# nekojara_board.net
KiCad netlist of a schematic drawn in EAGLE
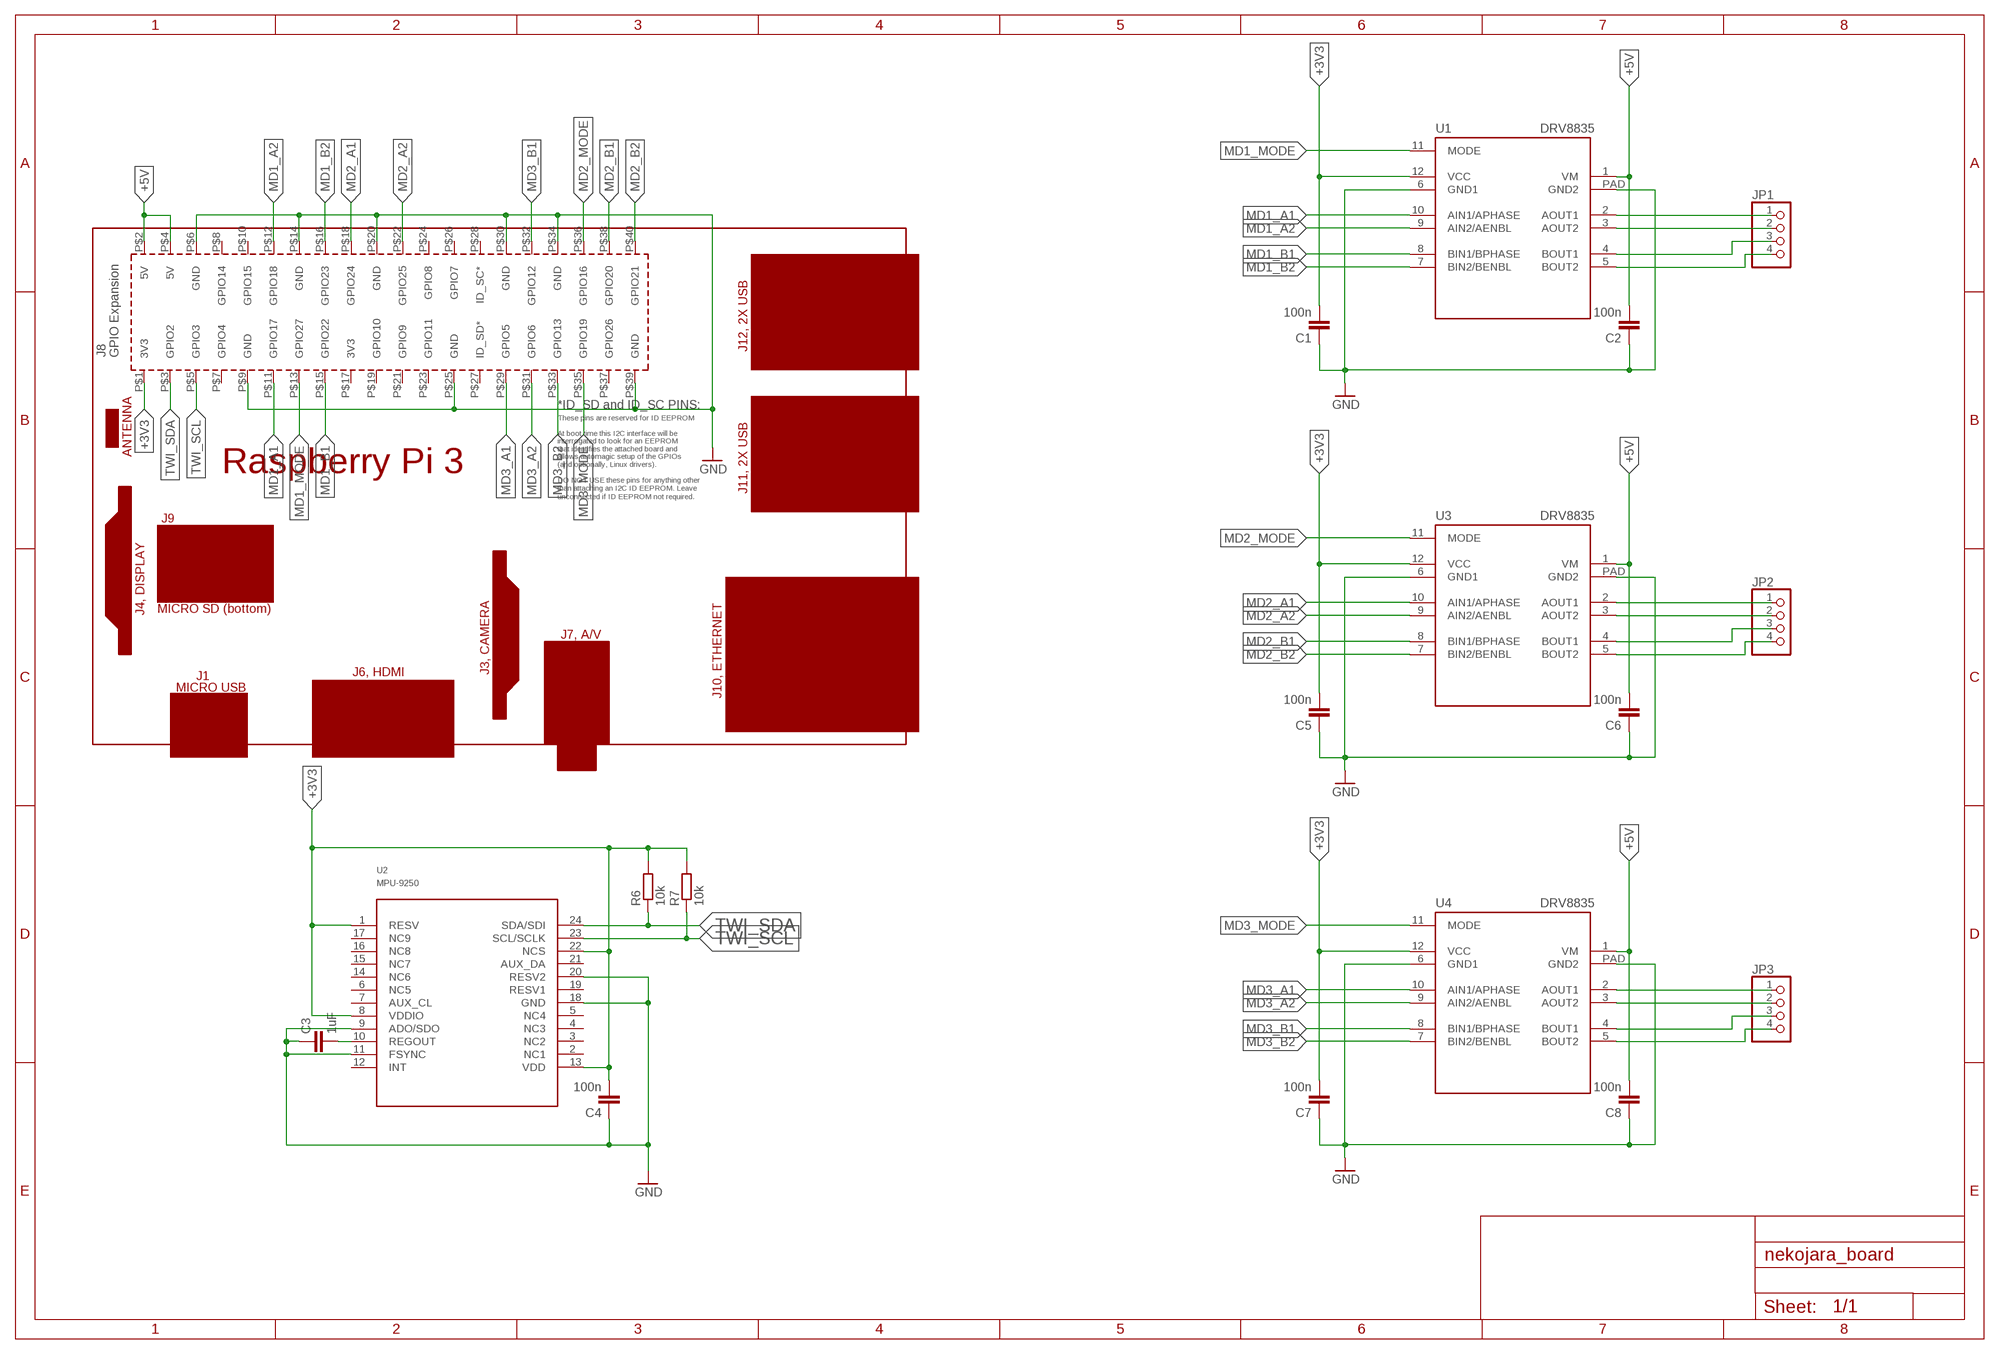
[diagram p0: schematic, sheet 1]

(export (version "E")
  (design (tool "Eeschema 10.0.6"))
  (components
    (comp (ref "C1")
      (value "100n")
      (footprint "eagle-import:C0402")
      (libsource (lib "eagle-import") (part "C-EUC0402"))
    )
    (comp (ref "C2")
      (value "100n")
      (footprint "eagle-import:C0402")
      (libsource (lib "eagle-import") (part "C-EUC0402"))
    )
    (comp (ref "C3")
      (value "1uF")
      (footprint "eagle-import:C0402")
      (libsource (lib "eagle-import") (part "C-EUC0402"))
    )
    (comp (ref "C4")
      (value "100n")
      (footprint "eagle-import:C0402")
      (libsource (lib "eagle-import") (part "C-EUC0402"))
    )
    (comp (ref "C5")
      (value "100n")
      (footprint "eagle-import:C0402")
      (libsource (lib "eagle-import") (part "C-EUC0402"))
    )
    (comp (ref "C6")
      (value "100n")
      (footprint "eagle-import:C0402")
      (libsource (lib "eagle-import") (part "C-EUC0402"))
    )
    (comp (ref "C7")
      (value "100n")
      (footprint "eagle-import:C0402")
      (libsource (lib "eagle-import") (part "C-EUC0402"))
    )
    (comp (ref "C8")
      (value "100n")
      (footprint "eagle-import:C0402")
      (libsource (lib "eagle-import") (part "C-EUC0402"))
    )
    (comp (ref "JP1")
      (value "PINHD-1X4")
      (footprint "eagle-import:1X04")
      (libsource (lib "eagle-import") (part "PINHD-1X4"))
    )
    (comp (ref "JP2")
      (value "PINHD-1X4")
      (footprint "eagle-import:1X04")
      (libsource (lib "eagle-import") (part "PINHD-1X4"))
    )
    (comp (ref "JP3")
      (value "PINHD-1X4")
      (footprint "eagle-import:1X04")
      (libsource (lib "eagle-import") (part "PINHD-1X4"))
    )
    (comp (ref "PCB1")
      (value "RPI3")
      (footprint "eagle-import:RPI3")
      (libsource (lib "eagle-import") (part "RPI3"))
    )
    (comp (ref "R6")
      (value "10k")
      (footprint "eagle-import:R0402")
      (libsource (lib "eagle-import") (part "R-EU_R0402"))
    )
    (comp (ref "R7")
      (value "10k")
      (footprint "eagle-import:R0402")
      (libsource (lib "eagle-import") (part "R-EU_R0402"))
    )
    (comp (ref "U1")
      (value "DRV8835")
      (footprint "eagle-import:WSON_2X3")
      (libsource (lib "eagle-import") (part "DRV8835"))
    )
    (comp (ref "U2")
      (value "MPU-9250")
      (footprint "eagle-import:LEAD-QFN24")
      (libsource (lib "eagle-import") (part "MPU-9250"))
    )
    (comp (ref "U3")
      (value "DRV8835")
      (footprint "eagle-import:WSON_2X3")
      (libsource (lib "eagle-import") (part "DRV8835"))
    )
    (comp (ref "U4")
      (value "DRV8835")
      (footprint "eagle-import:WSON_2X3")
      (libsource (lib "eagle-import") (part "DRV8835"))
    )
  )
  (nets
    (net (code "1") (name "+3V3") (class "Default")
      (node (ref "C1") (pin "2") (pinfunction "2_2") (pintype "passive"))
      (node (ref "C4") (pin "2") (pinfunction "2_2") (pintype "passive"))
      (node (ref "C5") (pin "2") (pinfunction "2_2") (pintype "passive"))
      (node (ref "C7") (pin "2") (pinfunction "2_2") (pintype "passive"))
      (node (ref "PCB1") (pin "P$1") (pinfunction "3V3_P$1") (pintype "bidirectional"))
      (node (ref "R6") (pin "2") (pinfunction "2_2") (pintype "passive"))
      (node (ref "R7") (pin "2") (pinfunction "2_2") (pintype "passive"))
      (node (ref "U1") (pin "12") (pinfunction "VCC_12") (pintype "bidirectional"))
      (node (ref "U2") (pin "1") (pinfunction "RESV_1") (pintype "bidirectional"))
      (node (ref "U2") (pin "13") (pinfunction "VDD_13") (pintype "bidirectional"))
      (node (ref "U2") (pin "22") (pinfunction "NCS_22") (pintype "bidirectional"))
      (node (ref "U2") (pin "8") (pinfunction "VDDIO_8") (pintype "bidirectional"))
      (node (ref "U3") (pin "12") (pinfunction "VCC_12") (pintype "bidirectional"))
      (node (ref "U4") (pin "12") (pinfunction "VCC_12") (pintype "bidirectional"))
    )
    (net (code "2") (name "+5V") (class "Default")
      (node (ref "C2") (pin "2") (pinfunction "2_2") (pintype "passive"))
      (node (ref "C6") (pin "2") (pinfunction "2_2") (pintype "passive"))
      (node (ref "C8") (pin "2") (pinfunction "2_2") (pintype "passive"))
      (node (ref "PCB1") (pin "P$2") (pinfunction "5V_P$2") (pintype "bidirectional"))
      (node (ref "PCB1") (pin "P$4") (pinfunction "5V_P$4") (pintype "bidirectional"))
      (node (ref "U1") (pin "1") (pinfunction "VM_1") (pintype "bidirectional"))
      (node (ref "U3") (pin "1") (pinfunction "VM_1") (pintype "bidirectional"))
      (node (ref "U4") (pin "1") (pinfunction "VM_1") (pintype "bidirectional"))
    )
    (net (code "3") (name "GND") (class "Default")
      (node (ref "C1") (pin "1") (pinfunction "1_1") (pintype "passive"))
      (node (ref "C2") (pin "1") (pinfunction "1_1") (pintype "passive"))
      (node (ref "C3") (pin "1") (pinfunction "1_1") (pintype "passive"))
      (node (ref "C4") (pin "1") (pinfunction "1_1") (pintype "passive"))
      (node (ref "C5") (pin "1") (pinfunction "1_1") (pintype "passive"))
      (node (ref "C6") (pin "1") (pinfunction "1_1") (pintype "passive"))
      (node (ref "C7") (pin "1") (pinfunction "1_1") (pintype "passive"))
      (node (ref "C8") (pin "1") (pinfunction "1_1") (pintype "passive"))
      (node (ref "PCB1") (pin "P$14") (pinfunction "GND_P$14") (pintype "bidirectional"))
      (node (ref "PCB1") (pin "P$20") (pinfunction "GND_P$20") (pintype "bidirectional"))
      (node (ref "PCB1") (pin "P$25") (pinfunction "GND_P$25") (pintype "bidirectional"))
      (node (ref "PCB1") (pin "P$30") (pinfunction "GND_P$30") (pintype "bidirectional"))
      (node (ref "PCB1") (pin "P$34") (pinfunction "GND_P$34") (pintype "bidirectional"))
      (node (ref "PCB1") (pin "P$39") (pinfunction "GND_P$39") (pintype "bidirectional"))
      (node (ref "PCB1") (pin "P$6") (pinfunction "GND_P$6") (pintype "bidirectional"))
      (node (ref "PCB1") (pin "P$9") (pinfunction "GND_P$9") (pintype "bidirectional"))
      (node (ref "U1") (pin "6") (pinfunction "GND1_6") (pintype "bidirectional"))
      (node (ref "U1") (pin "PAD") (pinfunction "GND2_PAD") (pintype "bidirectional"))
      (node (ref "U2") (pin "11") (pinfunction "FSYNC_11") (pintype "bidirectional"))
      (node (ref "U2") (pin "18") (pinfunction "GND_18") (pintype "bidirectional"))
      (node (ref "U2") (pin "20") (pinfunction "RESV2_20") (pintype "bidirectional"))
      (node (ref "U2") (pin "9") (pinfunction "ADO/SDO_9") (pintype "bidirectional"))
      (node (ref "U3") (pin "6") (pinfunction "GND1_6") (pintype "bidirectional"))
      (node (ref "U3") (pin "PAD") (pinfunction "GND2_PAD") (pintype "bidirectional"))
      (node (ref "U4") (pin "6") (pinfunction "GND1_6") (pintype "bidirectional"))
      (node (ref "U4") (pin "PAD") (pinfunction "GND2_PAD") (pintype "bidirectional"))
    )
    (net (code "4") (name "MD1_A1") (class "Default")
      (node (ref "PCB1") (pin "P$11") (pinfunction "GPIO17_P$11") (pintype "bidirectional"))
      (node (ref "U1") (pin "10") (pinfunction "AIN1/APHASE_10") (pintype "bidirectional"))
    )
    (net (code "5") (name "MD1_A2") (class "Default")
      (node (ref "PCB1") (pin "P$12") (pinfunction "GPIO18_P$12") (pintype "bidirectional"))
      (node (ref "U1") (pin "9") (pinfunction "AIN2/AENBL_9") (pintype "bidirectional"))
    )
    (net (code "6") (name "MD1_B1") (class "Default")
      (node (ref "PCB1") (pin "P$15") (pinfunction "GPIO22_P$15") (pintype "bidirectional"))
      (node (ref "U1") (pin "8") (pinfunction "BIN1/BPHASE_8") (pintype "bidirectional"))
    )
    (net (code "7") (name "MD1_B2") (class "Default")
      (node (ref "PCB1") (pin "P$16") (pinfunction "GPIO23_P$16") (pintype "bidirectional"))
      (node (ref "U1") (pin "7") (pinfunction "BIN2/BENBL_7") (pintype "bidirectional"))
    )
    (net (code "8") (name "MD1_MODE") (class "Default")
      (node (ref "PCB1") (pin "P$13") (pinfunction "GPIO27_P$13") (pintype "bidirectional"))
      (node (ref "U1") (pin "11") (pinfunction "MODE_11") (pintype "bidirectional"))
    )
    (net (code "9") (name "MD2_A1") (class "Default")
      (node (ref "PCB1") (pin "P$18") (pinfunction "GPIO24_P$18") (pintype "bidirectional"))
      (node (ref "U3") (pin "10") (pinfunction "AIN1/APHASE_10") (pintype "bidirectional"))
    )
    (net (code "10") (name "MD2_A2") (class "Default")
      (node (ref "PCB1") (pin "P$22") (pinfunction "GPIO25_P$22") (pintype "bidirectional"))
      (node (ref "U3") (pin "9") (pinfunction "AIN2/AENBL_9") (pintype "bidirectional"))
    )
    (net (code "11") (name "MD2_B1") (class "Default")
      (node (ref "PCB1") (pin "P$38") (pinfunction "GPIO20_P$38") (pintype "bidirectional"))
      (node (ref "U3") (pin "8") (pinfunction "BIN1/BPHASE_8") (pintype "bidirectional"))
    )
    (net (code "12") (name "MD2_B2") (class "Default")
      (node (ref "PCB1") (pin "P$40") (pinfunction "GPIO21_P$40") (pintype "bidirectional"))
      (node (ref "U3") (pin "7") (pinfunction "BIN2/BENBL_7") (pintype "bidirectional"))
    )
    (net (code "13") (name "MD2_MODE") (class "Default")
      (node (ref "PCB1") (pin "P$36") (pinfunction "GPIO16_P$36") (pintype "bidirectional"))
      (node (ref "U3") (pin "11") (pinfunction "MODE_11") (pintype "bidirectional"))
    )
    (net (code "14") (name "MD3_A1") (class "Default")
      (node (ref "PCB1") (pin "P$29") (pinfunction "GPIO5_P$29") (pintype "bidirectional"))
      (node (ref "U4") (pin "10") (pinfunction "AIN1/APHASE_10") (pintype "bidirectional"))
    )
    (net (code "15") (name "MD3_A2") (class "Default")
      (node (ref "PCB1") (pin "P$31") (pinfunction "GPIO6_P$31") (pintype "bidirectional"))
      (node (ref "U4") (pin "9") (pinfunction "AIN2/AENBL_9") (pintype "bidirectional"))
    )
    (net (code "16") (name "MD3_B1") (class "Default")
      (node (ref "PCB1") (pin "P$32") (pinfunction "GPIO12_P$32") (pintype "bidirectional"))
      (node (ref "U4") (pin "8") (pinfunction "BIN1/BPHASE_8") (pintype "bidirectional"))
    )
    (net (code "17") (name "MD3_B2") (class "Default")
      (node (ref "PCB1") (pin "P$33") (pinfunction "GPIO13_P$33") (pintype "bidirectional"))
      (node (ref "U4") (pin "7") (pinfunction "BIN2/BENBL_7") (pintype "bidirectional"))
    )
    (net (code "18") (name "MD3_MODE") (class "Default")
      (node (ref "PCB1") (pin "P$35") (pinfunction "GPIO19_P$35") (pintype "bidirectional"))
      (node (ref "U4") (pin "11") (pinfunction "MODE_11") (pintype "bidirectional"))
    )
    (net (code "19") (name "Net-(U1-AOUT1)") (class "Default")
      (node (ref "JP1") (pin "1") (pinfunction "1_1") (pintype "passive"))
      (node (ref "U1") (pin "2") (pinfunction "AOUT1_2") (pintype "bidirectional"))
    )
    (net (code "20") (name "Net-(U1-AOUT2)") (class "Default")
      (node (ref "JP1") (pin "2") (pinfunction "2_2") (pintype "passive"))
      (node (ref "U1") (pin "3") (pinfunction "AOUT2_3") (pintype "bidirectional"))
    )
    (net (code "21") (name "Net-(U1-BOUT1)") (class "Default")
      (node (ref "JP1") (pin "3") (pinfunction "3_3") (pintype "passive"))
      (node (ref "U1") (pin "4") (pinfunction "BOUT1_4") (pintype "bidirectional"))
    )
    (net (code "22") (name "Net-(U1-BOUT2)") (class "Default")
      (node (ref "JP1") (pin "4") (pinfunction "4_4") (pintype "passive"))
      (node (ref "U1") (pin "5") (pinfunction "BOUT2_5") (pintype "bidirectional"))
    )
    (net (code "23") (name "Net-(U2-REGOUT)") (class "Default")
      (node (ref "C3") (pin "2") (pinfunction "2_2") (pintype "passive"))
      (node (ref "U2") (pin "10") (pinfunction "REGOUT_10") (pintype "bidirectional"))
    )
    (net (code "24") (name "Net-(U3-AOUT1)") (class "Default")
      (node (ref "JP2") (pin "1") (pinfunction "1_1") (pintype "passive"))
      (node (ref "U3") (pin "2") (pinfunction "AOUT1_2") (pintype "bidirectional"))
    )
    (net (code "25") (name "Net-(U3-AOUT2)") (class "Default")
      (node (ref "JP2") (pin "2") (pinfunction "2_2") (pintype "passive"))
      (node (ref "U3") (pin "3") (pinfunction "AOUT2_3") (pintype "bidirectional"))
    )
    (net (code "26") (name "Net-(U3-BOUT1)") (class "Default")
      (node (ref "JP2") (pin "3") (pinfunction "3_3") (pintype "passive"))
      (node (ref "U3") (pin "4") (pinfunction "BOUT1_4") (pintype "bidirectional"))
    )
    (net (code "27") (name "Net-(U3-BOUT2)") (class "Default")
      (node (ref "JP2") (pin "4") (pinfunction "4_4") (pintype "passive"))
      (node (ref "U3") (pin "5") (pinfunction "BOUT2_5") (pintype "bidirectional"))
    )
    (net (code "28") (name "Net-(U4-AOUT1)") (class "Default")
      (node (ref "JP3") (pin "1") (pinfunction "1_1") (pintype "passive"))
      (node (ref "U4") (pin "2") (pinfunction "AOUT1_2") (pintype "bidirectional"))
    )
    (net (code "29") (name "Net-(U4-AOUT2)") (class "Default")
      (node (ref "JP3") (pin "2") (pinfunction "2_2") (pintype "passive"))
      (node (ref "U4") (pin "3") (pinfunction "AOUT2_3") (pintype "bidirectional"))
    )
    (net (code "30") (name "Net-(U4-BOUT1)") (class "Default")
      (node (ref "JP3") (pin "3") (pinfunction "3_3") (pintype "passive"))
      (node (ref "U4") (pin "4") (pinfunction "BOUT1_4") (pintype "bidirectional"))
    )
    (net (code "31") (name "Net-(U4-BOUT2)") (class "Default")
      (node (ref "JP3") (pin "4") (pinfunction "4_4") (pintype "passive"))
      (node (ref "U4") (pin "5") (pinfunction "BOUT2_5") (pintype "bidirectional"))
    )
    (net (code "32") (name "TWI_SCL") (class "Default")
      (node (ref "PCB1") (pin "P$5") (pinfunction "GPIO3_P$5") (pintype "bidirectional"))
      (node (ref "R7") (pin "1") (pinfunction "1_1") (pintype "passive"))
      (node (ref "U2") (pin "23") (pinfunction "SCL/SCLK_23") (pintype "bidirectional"))
    )
    (net (code "33") (name "TWI_SDA") (class "Default")
      (node (ref "PCB1") (pin "P$3") (pinfunction "GPIO2_P$3") (pintype "bidirectional"))
      (node (ref "R6") (pin "1") (pinfunction "1_1") (pintype "passive"))
      (node (ref "U2") (pin "24") (pinfunction "SDA/SDI_24") (pintype "bidirectional"))
    )
    (net (code "34") (name "unconnected-(PCB1-3V3-PadP$17)") (class "Default")
      (node (ref "PCB1") (pin "P$17") (pinfunction "3V3_P$17") (pintype "bidirectional"))
    )
    (net (code "35") (name "unconnected-(PCB1-GPIO4-PadP$7)") (class "Default")
      (node (ref "PCB1") (pin "P$7") (pinfunction "GPIO4_P$7") (pintype "bidirectional"))
    )
    (net (code "36") (name "unconnected-(PCB1-GPIO7-PadP$26)") (class "Default")
      (node (ref "PCB1") (pin "P$26") (pinfunction "GPIO7_P$26") (pintype "bidirectional"))
    )
    (net (code "37") (name "unconnected-(PCB1-GPIO8-PadP$24)") (class "Default")
      (node (ref "PCB1") (pin "P$24") (pinfunction "GPIO8_P$24") (pintype "bidirectional"))
    )
    (net (code "38") (name "unconnected-(PCB1-GPIO9-PadP$21)") (class "Default")
      (node (ref "PCB1") (pin "P$21") (pinfunction "GPIO9_P$21") (pintype "bidirectional"))
    )
    (net (code "39") (name "unconnected-(PCB1-GPIO10-PadP$19)") (class "Default")
      (node (ref "PCB1") (pin "P$19") (pinfunction "GPIO10_P$19") (pintype "bidirectional"))
    )
    (net (code "40") (name "unconnected-(PCB1-GPIO11-PadP$23)") (class "Default")
      (node (ref "PCB1") (pin "P$23") (pinfunction "GPIO11_P$23") (pintype "bidirectional"))
    )
    (net (code "41") (name "unconnected-(PCB1-GPIO14-PadP$8)") (class "Default")
      (node (ref "PCB1") (pin "P$8") (pinfunction "GPIO14_P$8") (pintype "bidirectional"))
    )
    (net (code "42") (name "unconnected-(PCB1-GPIO15-PadP$10)") (class "Default")
      (node (ref "PCB1") (pin "P$10") (pinfunction "GPIO15_P$10") (pintype "bidirectional"))
    )
    (net (code "43") (name "unconnected-(PCB1-GPIO26-PadP$37)") (class "Default")
      (node (ref "PCB1") (pin "P$37") (pinfunction "GPIO26_P$37") (pintype "bidirectional"))
    )
    (net (code "44") (name "unconnected-(PCB1-ID_SC*-PadP$28)") (class "Default")
      (node (ref "PCB1") (pin "P$28") (pinfunction "ID_SC*_P$28") (pintype "bidirectional"))
    )
    (net (code "45") (name "unconnected-(PCB1-ID_SD*-PadP$27)") (class "Default")
      (node (ref "PCB1") (pin "P$27") (pinfunction "ID_SD*_P$27") (pintype "bidirectional"))
    )
    (net (code "46") (name "unconnected-(U2-AUX_CL-Pad7)") (class "Default")
      (node (ref "U2") (pin "7") (pinfunction "AUX_CL_7") (pintype "bidirectional"))
    )
    (net (code "47") (name "unconnected-(U2-AUX_DA-Pad21)") (class "Default")
      (node (ref "U2") (pin "21") (pinfunction "AUX_DA_21") (pintype "bidirectional"))
    )
    (net (code "48") (name "unconnected-(U2-INT-Pad12)") (class "Default")
      (node (ref "U2") (pin "12") (pinfunction "INT_12") (pintype "bidirectional"))
    )
    (net (code "49") (name "unconnected-(U2-NC1-Pad2)") (class "Default")
      (node (ref "U2") (pin "2") (pinfunction "NC1_2") (pintype "bidirectional"))
    )
    (net (code "50") (name "unconnected-(U2-NC2-Pad3)") (class "Default")
      (node (ref "U2") (pin "3") (pinfunction "NC2_3") (pintype "bidirectional"))
    )
    (net (code "51") (name "unconnected-(U2-NC3-Pad4)") (class "Default")
      (node (ref "U2") (pin "4") (pinfunction "NC3_4") (pintype "bidirectional"))
    )
    (net (code "52") (name "unconnected-(U2-NC4-Pad5)") (class "Default")
      (node (ref "U2") (pin "5") (pinfunction "NC4_5") (pintype "bidirectional"))
    )
    (net (code "53") (name "unconnected-(U2-NC5-Pad6)") (class "Default")
      (node (ref "U2") (pin "6") (pinfunction "NC5_6") (pintype "bidirectional"))
    )
    (net (code "54") (name "unconnected-(U2-NC6-Pad14)") (class "Default")
      (node (ref "U2") (pin "14") (pinfunction "NC6_14") (pintype "bidirectional"))
    )
    (net (code "55") (name "unconnected-(U2-NC7-Pad15)") (class "Default")
      (node (ref "U2") (pin "15") (pinfunction "NC7_15") (pintype "bidirectional"))
    )
    (net (code "56") (name "unconnected-(U2-NC8-Pad16)") (class "Default")
      (node (ref "U2") (pin "16") (pinfunction "NC8_16") (pintype "bidirectional"))
    )
    (net (code "57") (name "unconnected-(U2-NC9-Pad17)") (class "Default")
      (node (ref "U2") (pin "17") (pinfunction "NC9_17") (pintype "bidirectional"))
    )
    (net (code "58") (name "unconnected-(U2-RESV1-Pad19)") (class "Default")
      (node (ref "U2") (pin "19") (pinfunction "RESV1_19") (pintype "bidirectional"))
    )
  )
)
